# ampli.net
KiCad netlist of a schematic drawn in EAGLE
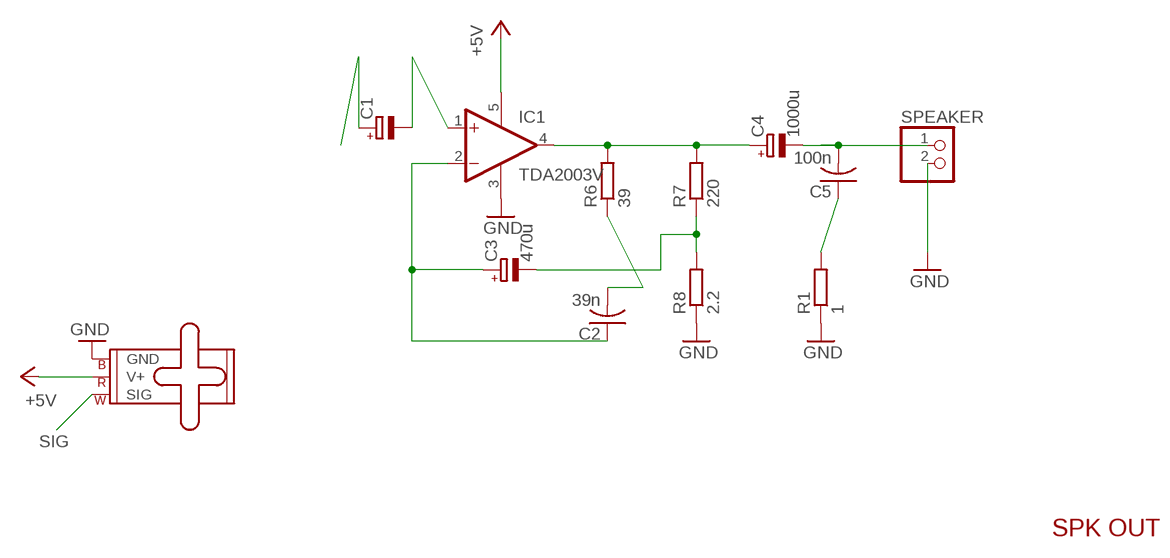
[diagram p0: schematic, sheet 1]

(export (version "E")
  (design (tool "Eeschema 10.0.6"))
  (components
    (comp (ref "C1")
      (value "CPOL-EUE2.5-6")
      (footprint "eagle-import:E2,5-6")
      (libsource (lib "eagle-import") (part "CPOL-EUE2.5-6"))
    )
    (comp (ref "C2")
      (value "39n")
      (footprint "eagle-import:C0805")
      (libsource (lib "eagle-import") (part "C-USC0805"))
    )
    (comp (ref "C3")
      (value "470u")
      (footprint "eagle-import:E2,5-6")
      (libsource (lib "eagle-import") (part "CPOL-EUE2.5-6"))
    )
    (comp (ref "C4")
      (value "1000u")
      (footprint "eagle-import:E2,5-6")
      (libsource (lib "eagle-import") (part "CPOL-EUE2.5-6"))
    )
    (comp (ref "C5")
      (value "100n")
      (footprint "eagle-import:C0805")
      (libsource (lib "eagle-import") (part "C-USC0805"))
    )
    (comp (ref "IC1")
      (value "TDA2003V")
      (footprint "eagle-import:CB360")
      (libsource (lib "eagle-import") (part "TDA2003V"))
    )
    (comp (ref "LED")
      (value "SMALL_SERVO")
      (footprint "eagle-import:1X03")
      (libsource (lib "eagle-import") (part "SMALL_SERVO"))
    )
    (comp (ref "R1")
      (value "1")
      (footprint "eagle-import:R0805")
      (libsource (lib "eagle-import") (part "R-EU_R0805"))
    )
    (comp (ref "R6")
      (value "39")
      (footprint "eagle-import:R0805")
      (libsource (lib "eagle-import") (part "R-EU_R0805"))
    )
    (comp (ref "R7")
      (value "220")
      (footprint "eagle-import:R0805")
      (libsource (lib "eagle-import") (part "R-EU_R0805"))
    )
    (comp (ref "R8")
      (value "2.2")
      (footprint "eagle-import:R0805")
      (libsource (lib "eagle-import") (part "R-EU_R0805"))
    )
    (comp (ref "SPEAKER")
      (value "PINHD-1X2")
      (footprint "eagle-import:1X02")
      (libsource (lib "eagle-import") (part "PINHD-1X2"))
    )
  )
  (nets
    (net (code "1") (name "+5V") (class "Default")
      (node (ref "IC1") (pin "5") (pinfunction "V+_5") (pintype "power_in"))
      (node (ref "LED") (pin "2") (pinfunction "V+_2") (pintype "bidirectional"))
    )
    (net (code "2") (name "/SIG") (class "Default")
      (node (ref "C1") (pin "+") (pinfunction "+_+") (pintype "passive"))
      (node (ref "LED") (pin "1") (pinfunction "SIG_1") (pintype "bidirectional"))
    )
    (net (code "3") (name "GND") (class "Default")
      (node (ref "IC1") (pin "3") (pinfunction "GND_3") (pintype "power_in"))
      (node (ref "LED") (pin "3") (pinfunction "GND_3") (pintype "bidirectional"))
      (node (ref "R1") (pin "1") (pinfunction "1_1") (pintype "passive"))
      (node (ref "R8") (pin "1") (pinfunction "1_1") (pintype "passive"))
      (node (ref "SPEAKER") (pin "2") (pinfunction "2_2") (pintype "passive"))
    )
    (net (code "4") (name "Net-(C2-Pad2)") (class "Default")
      (node (ref "C2") (pin "2") (pinfunction "2_2") (pintype "passive"))
      (node (ref "R6") (pin "1") (pinfunction "1_1") (pintype "passive"))
    )
    (net (code "5") (name "Net-(C3-Pad-)") (class "Default")
      (node (ref "C3") (pin "-") (pinfunction "-_-") (pintype "passive"))
      (node (ref "R7") (pin "1") (pinfunction "1_1") (pintype "passive"))
      (node (ref "R8") (pin "2") (pinfunction "2_2") (pintype "passive"))
    )
    (net (code "6") (name "Net-(C4-Pad-)") (class "Default")
      (node (ref "C4") (pin "-") (pinfunction "-_-") (pintype "passive"))
      (node (ref "C5") (pin "2") (pinfunction "2_2") (pintype "passive"))
      (node (ref "SPEAKER") (pin "1") (pinfunction "1_1") (pintype "passive"))
    )
    (net (code "7") (name "Net-(C5-Pad1)") (class "Default")
      (node (ref "C5") (pin "1") (pinfunction "1_1") (pintype "passive"))
      (node (ref "R1") (pin "2") (pinfunction "2_2") (pintype "passive"))
    )
    (net (code "8") (name "Net-(IC1-+IN)") (class "Default")
      (node (ref "C1") (pin "-") (pinfunction "-_-") (pintype "passive"))
      (node (ref "IC1") (pin "1") (pinfunction "+IN_1") (pintype "input"))
    )
    (net (code "9") (name "Net-(IC1--IN)") (class "Default")
      (node (ref "C2") (pin "1") (pinfunction "1_1") (pintype "passive"))
      (node (ref "C3") (pin "+") (pinfunction "+_+") (pintype "passive"))
      (node (ref "IC1") (pin "2") (pinfunction "-IN_2") (pintype "input"))
    )
    (net (code "10") (name "Net-(IC1-OUT)") (class "Default")
      (node (ref "C4") (pin "+") (pinfunction "+_+") (pintype "passive"))
      (node (ref "IC1") (pin "4") (pinfunction "OUT_4") (pintype "output"))
      (node (ref "R6") (pin "2") (pinfunction "2_2") (pintype "passive"))
      (node (ref "R7") (pin "2") (pinfunction "2_2") (pintype "passive"))
    )
  )
)
